# BlindController.net
KiCad netlist of a schematic drawn in Altium Designer
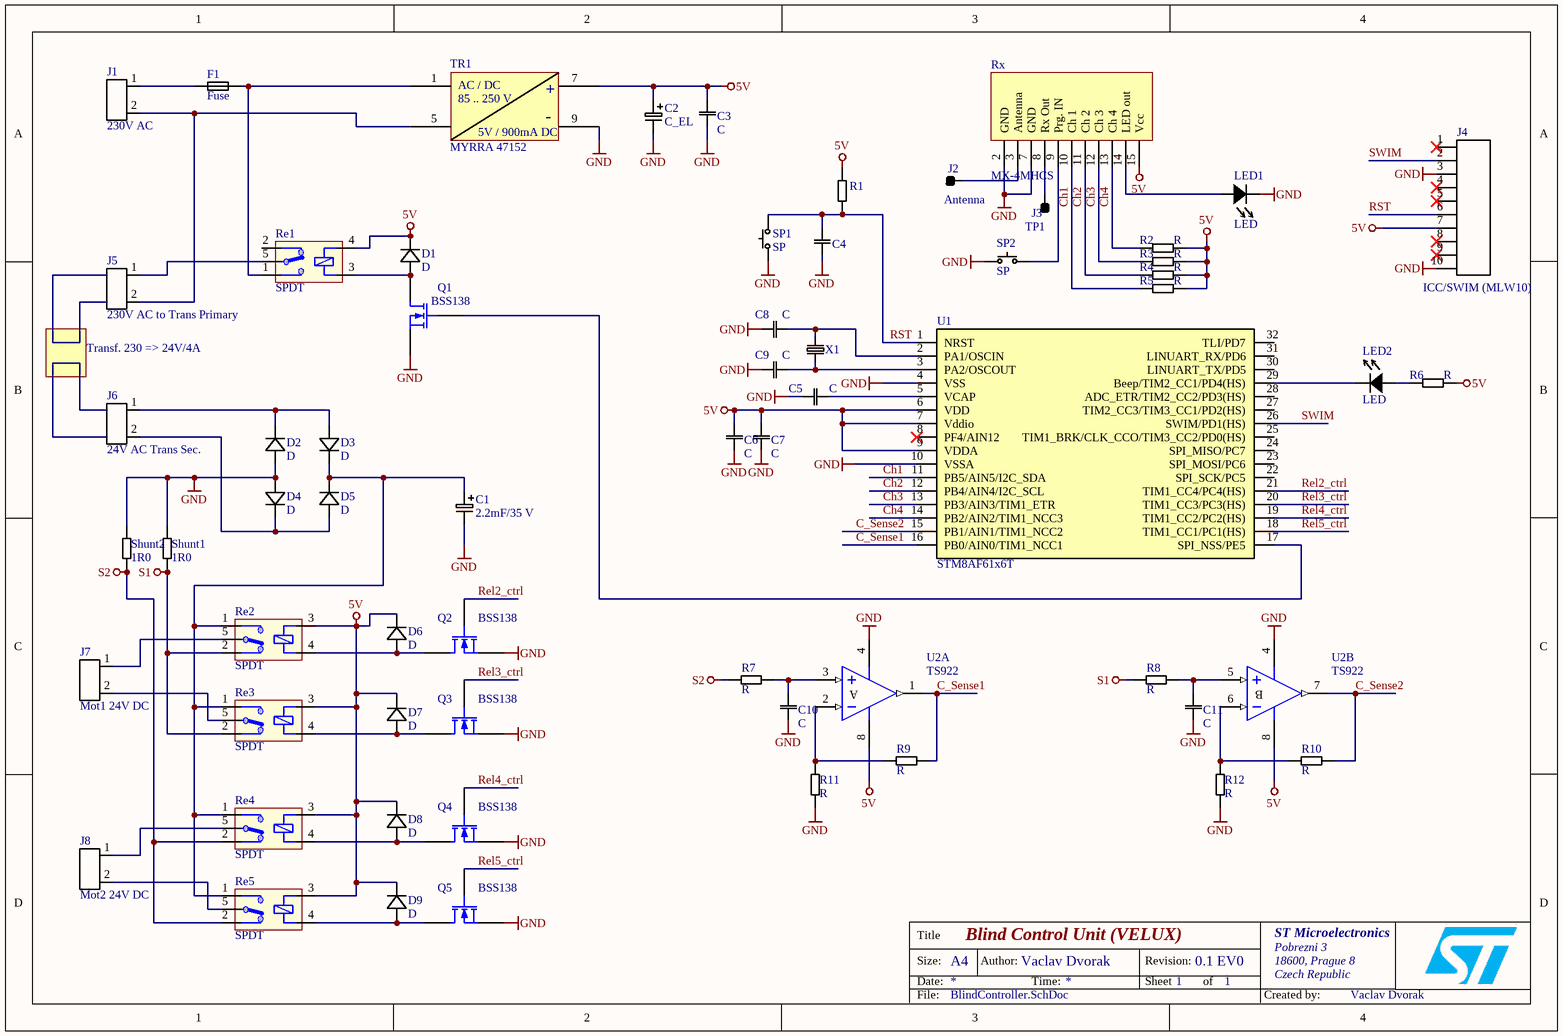
[diagram p0: BlindController.SchDoc]

(export (version "E")
  (design (tool "Eeschema 10.0.6"))
  (components
    (comp (ref "C1")
      (value "2.2mF/35 V")
      (footprint "EL_10X13")
      (libsource (lib "ABU_standard") (part "C_EL_1"))
    )
    (comp (ref "C2") (value "C_EL") (footprint "EL_5x11") (libsource (lib "ABU_standard") (part "C_EL")))
    (comp (ref "C3") (value "C") (footprint "ABU_standard:C0805") (libsource (lib "ABU_standard") (part "C")))
    (comp (ref "C4") (value "~") (footprint "ABU_standard:C0805") (libsource (lib "*") (part "C")))
    (comp (ref "C5") (value "C") (footprint "C0805") (libsource (lib "ABU_standard") (part "C")))
    (comp (ref "C6") (value "C") (footprint "ABU_standard:C0805") (libsource (lib "ABU_standard") (part "C")))
    (comp (ref "C7") (value "C") (footprint "ABU_standard:C0805") (libsource (lib "ABU_standard") (part "C")))
    (comp (ref "C8") (value "C") (footprint "ABU_standard:C0805") (libsource (lib "ABU_STANDARD") (part "C")))
    (comp (ref "C9") (value "C") (footprint "ABU_standard:C0805") (libsource (lib "ABU_STANDARD") (part "C")))
    (comp (ref "C10")
      (value "C")
      (footprint "ABU_standard:C0805")
      (libsource (lib "ABU_standard") (part "C"))
    )
    (comp (ref "C11")
      (value "C")
      (footprint "ABU_standard:C0805")
      (libsource (lib "ABU_standard") (part "C"))
    )
    (comp (ref "D1") (value "D") (footprint "SMA") (libsource (lib "ABU_standard") (part "D")))
    (comp (ref "D2") (value "D") (footprint "DO41") (libsource (lib "ABU_standard") (part "D")))
    (comp (ref "D3") (value "D") (footprint "DO41") (libsource (lib "ABU_standard") (part "D")))
    (comp (ref "D4") (value "D") (footprint "DO41") (libsource (lib "ABU_standard") (part "D")))
    (comp (ref "D5") (value "D") (footprint "DO41") (libsource (lib "ABU_standard") (part "D")))
    (comp (ref "D6") (value "D") (footprint "SMA") (libsource (lib "ABU_standard") (part "D")))
    (comp (ref "D7") (value "D") (footprint "SMA") (libsource (lib "ABU_standard") (part "D")))
    (comp (ref "D8") (value "D") (footprint "SMA") (libsource (lib "ABU_standard") (part "D")))
    (comp (ref "D9") (value "D") (footprint "SMA") (libsource (lib "ABU_standard") (part "D")))
    (comp (ref "F1") (value "Fuse") (footprint "AXIAL-0.5L") (libsource (lib "Private") (part "Fuse")))
    (comp (ref "J1") (value "230V AC") (footprint "ARK_2") (libsource (lib "ABU_standard") (part "CON_2")))
    (comp (ref "J2") (value "Antenna") (footprint "PIN") (libsource (lib "ABU_standard") (part "PIN")))
    (comp (ref "J3") (value "TP1") (footprint "PIN") (libsource (lib "") (part "PIN_1")))
    (comp (ref "J4") (value "ICC/SWIM (MLW10)") (footprint "MLW10") (libsource (lib "*") (part "CON_10")))
    (comp (ref "J5")
      (value "230V AC to Trans Primary")
      (footprint "ARK_2")
      (libsource (lib "ABU_standard") (part "CON_2"))
    )
    (comp (ref "J6")
      (value "24V AC Trans Sec.")
      (footprint "ARK_2")
      (libsource (lib "ABU_standard") (part "CON_2"))
    )
    (comp (ref "J7")
      (value "Mot1 24V DC")
      (footprint "ARK_2")
      (libsource (lib "ABU_standard") (part "CON_2"))
    )
    (comp (ref "J8")
      (value "Mot2 24V DC")
      (footprint "ARK_2")
      (libsource (lib "ABU_standard") (part "CON_2"))
    )
    (comp (ref "LED1") (value "LED") (footprint "LED_SMD") (libsource (lib "ABU_standard") (part "LED")))
    (comp (ref "LED2") (value "LED") (footprint "LED_SMD") (libsource (lib "ABU_standard") (part "LED")))
    (comp (ref "Q1")
      (value "BSS138")
      (footprint "SOT23")
      (description "N-Channel Enhancement Mode Vertical DMOS FET")
      (fields (field (name "PUBLISHER") "Altium Limited"))
      (libsource (lib "ABU_standard") (part "BSS138"))
    )
    (comp (ref "Q2")
      (value "BSS138")
      (footprint "SOT23")
      (description "N-Channel Enhancement Mode Vertical DMOS FET")
      (fields (field (name "PUBLISHER") "Altium Limited"))
      (libsource (lib "ABU_standard") (part "BSS138"))
    )
    (comp (ref "Q3")
      (value "BSS138")
      (footprint "SOT23")
      (description "N-Channel Enhancement Mode Vertical DMOS FET")
      (fields (field (name "PUBLISHER") "Altium Limited"))
      (libsource (lib "ABU_standard") (part "BSS138"))
    )
    (comp (ref "Q4")
      (value "BSS138")
      (footprint "SOT23")
      (description "N-Channel Enhancement Mode Vertical DMOS FET")
      (fields (field (name "PUBLISHER") "Altium Limited"))
      (libsource (lib "ABU_standard") (part "BSS138"))
    )
    (comp (ref "Q5")
      (value "BSS138")
      (footprint "SOT23")
      (description "N-Channel Enhancement Mode Vertical DMOS FET")
      (fields (field (name "PUBLISHER") "Altium Limited"))
      (libsource (lib "ABU_standard") (part "BSS138"))
    )
    (comp (ref "R1") (value "~") (footprint "R0805") (libsource (lib "*") (part "R")))
    (comp (ref "R2") (value "R") (footprint "R0805") (libsource (lib "ABU_standard") (part "R")))
    (comp (ref "R3") (value "R") (footprint "R0805") (libsource (lib "ABU_standard") (part "R")))
    (comp (ref "R4") (value "R") (footprint "R0805") (libsource (lib "ABU_standard") (part "R")))
    (comp (ref "R5") (value "R") (footprint "R0805") (libsource (lib "ABU_standard") (part "R")))
    (comp (ref "R6") (value "R") (footprint "R0805") (libsource (lib "ABU_standard") (part "R")))
    (comp (ref "R7") (value "R") (footprint "R0805") (libsource (lib "") (part "R_2")))
    (comp (ref "R8") (value "R") (footprint "R0805") (libsource (lib "") (part "R_2")))
    (comp (ref "R9") (value "R") (footprint "R0805") (libsource (lib "ABU_standard") (part "R")))
    (comp (ref "R10") (value "R") (footprint "R0805") (libsource (lib "ABU_standard") (part "R")))
    (comp (ref "R11") (value "R") (footprint "R0805") (libsource (lib "") (part "R_1")))
    (comp (ref "R12") (value "R") (footprint "R0805") (libsource (lib "") (part "R_1")))
    (comp (ref "Re1")
      (value "SPDT")
      (footprint "Rele_JS-K")
      (description "rele SPDT")
      (libsource (lib "") (part "Rele_SPDT_1"))
    )
    (comp (ref "Re2")
      (value "SPDT")
      (footprint "Rele_JS-K")
      (description "rele SPDT")
      (libsource (lib "Private") (part "Rele_SPDT"))
    )
    (comp (ref "Re3")
      (value "SPDT")
      (footprint "Rele_JS-K")
      (description "rele SPDT")
      (libsource (lib "Private") (part "Rele_SPDT"))
    )
    (comp (ref "Re4")
      (value "SPDT")
      (footprint "Rele_JS-K")
      (description "rele SPDT")
      (libsource (lib "Private") (part "Rele_SPDT"))
    )
    (comp (ref "Re5")
      (value "SPDT")
      (footprint "Rele_JS-K")
      (description "rele SPDT")
      (libsource (lib "Private") (part "Rele_SPDT"))
    )
    (comp (ref "Rx") (value "MX-4MHCS") (footprint "RX-4MHCS") (libsource (lib "Private") (part "RX-4MHCS")))
    (comp (ref "Shunt1") (value "1R0") (footprint "R Shunt S-2") (libsource (lib "") (part "R_1")))
    (comp (ref "Shunt2") (value "1R0") (footprint "R Shunt S-2") (libsource (lib "") (part "R_1")))
    (comp (ref "SP1") (value "SP") (footprint "DIP_PUSH_BUTTON") (libsource (lib "*") (part "SP")))
    (comp (ref "SP2") (value "SP") (footprint "DIP_PUSH_BUTTON") (libsource (lib "ABU_standard") (part "SP")))
    (comp (ref "TR1")
      (value "MYRRA 47152")
      (footprint "Private:Myrra47000")
      (description "AC/DC  IN:85..260 V AC(DC), OUT: 5V/900mA DC")
      (libsource (lib "Private") (part "MYRRA_AC_DC"))
    )
    (comp (ref "U1")
      (value "STM8AF61x6T")
      (footprint "QFP32")
      (libsource (lib "ABU_standard") (part "STM8AF61x6T"))
    )
    (comp (ref "U2")
      (value "TS922")
      (footprint "SO8_L")
      (description "Rail-to-Rail CMOS Dual Operational Amplifier")
      (fields (field (name "PUBLISHER") "Altium Limited"))
      (libsource (lib "ST Operational Amplifier") (part "TS912ID"))
    )
    (comp (ref "X1") (value "~") (footprint "HC-49U") (libsource (lib "ABU_STANDARD") (part "XTALL")))
  )
  (nets
    (net (code "1") (name "/C_Sense1") (class "Default")
      (node (ref "R9") (pin "1") (pinfunction "1_1") (pintype "passive"))
      (node (ref "U1") (pin "16") (pinfunction "PB0/AIN0/TIM1_NCC1_16") (pintype "passive"))
      (node (ref "U2") (pin "1") (pinfunction "OUT_1") (pintype "output"))
    )
    (net (code "2") (name "/C_Sense2") (class "Default")
      (node (ref "R10") (pin "1") (pinfunction "1_1") (pintype "passive"))
      (node (ref "U1") (pin "15") (pinfunction "PB1/AIN1/TIM1_NCC2_15") (pintype "passive"))
      (node (ref "U2") (pin "7") (pinfunction "OUT_7") (pintype "output"))
    )
    (net (code "3") (name "/Ch1") (class "Default")
      (node (ref "R5") (pin "2") (pinfunction "2_2") (pintype "passive"))
      (node (ref "Rx") (pin "10") (pinfunction "Ch_1_10") (pintype "passive"))
      (node (ref "U1") (pin "11") (pinfunction "PB5/AIN5/I2C_SDA_11") (pintype "passive"))
    )
    (net (code "4") (name "/Ch2") (class "Default")
      (node (ref "R4") (pin "2") (pinfunction "2_2") (pintype "passive"))
      (node (ref "Rx") (pin "11") (pinfunction "Ch_2_11") (pintype "passive"))
      (node (ref "U1") (pin "12") (pinfunction "PB4/AIN4/I2C_SCL_12") (pintype "passive"))
    )
    (net (code "5") (name "/Ch3") (class "Default")
      (node (ref "R3") (pin "2") (pinfunction "2_2") (pintype "passive"))
      (node (ref "Rx") (pin "12") (pinfunction "Ch_3_12") (pintype "passive"))
      (node (ref "U1") (pin "13") (pinfunction "PB3/AIN3/TIM1_ETR_13") (pintype "passive"))
    )
    (net (code "6") (name "/Ch4") (class "Default")
      (node (ref "R2") (pin "2") (pinfunction "2_2") (pintype "passive"))
      (node (ref "Rx") (pin "13") (pinfunction "Ch_4_13") (pintype "passive"))
      (node (ref "U1") (pin "14") (pinfunction "PB2/AIN2/TIM1_NCC3_14") (pintype "passive"))
    )
    (net (code "7") (name "/RST") (class "Default")
      (node (ref "C4") (pin "2") (pinfunction "2_2") (pintype "passive"))
      (node (ref "J4") (pin "6") (pinfunction "6_6") (pintype "passive"))
      (node (ref "R1") (pin "2") (pinfunction "2_2") (pintype "passive"))
      (node (ref "SP1") (pin "2") (pinfunction "2_2") (pintype "passive"))
      (node (ref "U1") (pin "1") (pinfunction "NRST_1") (pintype "passive"))
    )
    (net (code "8") (name "/Rel2_ctrl") (class "Default")
      (node (ref "Q2") (pin "1") (pinfunction "G_1") (pintype "passive"))
      (node (ref "U1") (pin "21") (pinfunction "TIM1_CC4/PC4(HS)_21") (pintype "passive"))
    )
    (net (code "9") (name "/Rel3_ctrl") (class "Default")
      (node (ref "Q3") (pin "1") (pinfunction "G_1") (pintype "passive"))
      (node (ref "U1") (pin "20") (pinfunction "TIM1_CC3/PC3(HS)_20") (pintype "passive"))
    )
    (net (code "10") (name "/Rel4_ctrl") (class "Default")
      (node (ref "Q4") (pin "1") (pinfunction "G_1") (pintype "passive"))
      (node (ref "U1") (pin "19") (pinfunction "TIM1_CC2/PC2(HS)_19") (pintype "passive"))
    )
    (net (code "11") (name "/Rel5_ctrl") (class "Default")
      (node (ref "Q5") (pin "1") (pinfunction "G_1") (pintype "passive"))
      (node (ref "U1") (pin "18") (pinfunction "TIM1_CC1/PC1(HS)_18") (pintype "passive"))
    )
    (net (code "12") (name "/SWIM") (class "Default")
      (node (ref "J4") (pin "2") (pinfunction "2_2") (pintype "passive"))
      (node (ref "U1") (pin "26") (pinfunction "SWIM/PD1(HS)_26") (pintype "passive"))
    )
    (net (code "13") (name "5V") (class "Default")
      (node (ref "C2") (pin "1") (pinfunction "1_1") (pintype "passive"))
      (node (ref "C3") (pin "2") (pinfunction "2_2") (pintype "passive"))
      (node (ref "C6") (pin "2") (pinfunction "2_2") (pintype "passive"))
      (node (ref "C7") (pin "2") (pinfunction "2_2") (pintype "passive"))
      (node (ref "D1") (pin "2") (pinfunction "K_2") (pintype "passive"))
      (node (ref "D6") (pin "2") (pinfunction "K_2") (pintype "passive"))
      (node (ref "D7") (pin "2") (pinfunction "K_2") (pintype "passive"))
      (node (ref "D8") (pin "2") (pinfunction "K_2") (pintype "passive"))
      (node (ref "D9") (pin "2") (pinfunction "K_2") (pintype "passive"))
      (node (ref "J4") (pin "7") (pinfunction "7_7") (pintype "passive"))
      (node (ref "R1") (pin "1") (pinfunction "1_1") (pintype "passive"))
      (node (ref "R2") (pin "1") (pinfunction "1_1") (pintype "passive"))
      (node (ref "R3") (pin "1") (pinfunction "1_1") (pintype "passive"))
      (node (ref "R4") (pin "1") (pinfunction "1_1") (pintype "passive"))
      (node (ref "R5") (pin "1") (pinfunction "1_1") (pintype "passive"))
      (node (ref "R6") (pin "1") (pinfunction "1_1") (pintype "passive"))
      (node (ref "Re1") (pin "4") (pinfunction "4_4") (pintype "passive"))
      (node (ref "Re2") (pin "3") (pinfunction "3_3") (pintype "passive"))
      (node (ref "Re3") (pin "3") (pinfunction "3_3") (pintype "passive"))
      (node (ref "Re4") (pin "3") (pinfunction "3_3") (pintype "passive"))
      (node (ref "Re5") (pin "3") (pinfunction "3_3") (pintype "passive"))
      (node (ref "Rx") (pin "15") (pinfunction "Vcc_15") (pintype "passive"))
      (node (ref "TR1") (pin "7") (pinfunction "7_7") (pintype "passive"))
      (node (ref "U1") (pin "6") (pinfunction "VDD_6") (pintype "passive"))
      (node (ref "U1") (pin "7") (pinfunction "Vddio_7") (pintype "passive"))
      (node (ref "U1") (pin "9") (pinfunction "VDDA_9") (pintype "passive"))
      (node (ref "U2") (pin "8") (pinfunction "V+_8") (pintype "power_in"))
    )
    (net (code "14") (name "GND") (class "Default")
      (node (ref "C1") (pin "2") (pinfunction "2_2") (pintype "passive"))
      (node (ref "C10") (pin "1") (pinfunction "1_1") (pintype "passive"))
      (node (ref "C11") (pin "1") (pinfunction "1_1") (pintype "passive"))
      (node (ref "C2") (pin "2") (pinfunction "2_2") (pintype "passive"))
      (node (ref "C3") (pin "1") (pinfunction "1_1") (pintype "passive"))
      (node (ref "C4") (pin "1") (pinfunction "1_1") (pintype "passive"))
      (node (ref "C5") (pin "1") (pinfunction "1_1") (pintype "passive"))
      (node (ref "C6") (pin "1") (pinfunction "1_1") (pintype "passive"))
      (node (ref "C7") (pin "1") (pinfunction "1_1") (pintype "passive"))
      (node (ref "C8") (pin "1") (pinfunction "1_1") (pintype "passive"))
      (node (ref "C9") (pin "1") (pinfunction "1_1") (pintype "passive"))
      (node (ref "D2") (pin "1") (pinfunction "A_1") (pintype "passive"))
      (node (ref "D4") (pin "1") (pinfunction "A_1") (pintype "passive"))
      (node (ref "J4") (pin "10") (pinfunction "10_10") (pintype "passive"))
      (node (ref "J4") (pin "3") (pinfunction "3_3") (pintype "passive"))
      (node (ref "LED1") (pin "2") (pinfunction "K_2") (pintype "passive"))
      (node (ref "Q1") (pin "2") (pinfunction "S_2") (pintype "passive"))
      (node (ref "Q2") (pin "2") (pinfunction "S_2") (pintype "passive"))
      (node (ref "Q3") (pin "2") (pinfunction "S_2") (pintype "passive"))
      (node (ref "Q4") (pin "2") (pinfunction "S_2") (pintype "passive"))
      (node (ref "Q5") (pin "2") (pinfunction "S_2") (pintype "passive"))
      (node (ref "R11") (pin "2") (pinfunction "2_2") (pintype "passive"))
      (node (ref "R12") (pin "2") (pinfunction "2_2") (pintype "passive"))
      (node (ref "Rx") (pin "2") (pinfunction "GND_2") (pintype "passive"))
      (node (ref "Rx") (pin "7") (pinfunction "GND_7") (pintype "passive"))
      (node (ref "SP1") (pin "1") (pinfunction "1_1") (pintype "passive"))
      (node (ref "SP2") (pin "1") (pinfunction "1_1") (pintype "passive"))
      (node (ref "Shunt1") (pin "1") (pinfunction "1_1") (pintype "passive"))
      (node (ref "Shunt2") (pin "1") (pinfunction "1_1") (pintype "passive"))
      (node (ref "TR1") (pin "9") (pinfunction "9_9") (pintype "passive"))
      (node (ref "U1") (pin "10") (pinfunction "VSSA_10") (pintype "passive"))
      (node (ref "U1") (pin "4") (pinfunction "VSS_4") (pintype "passive"))
      (node (ref "U2") (pin "4") (pinfunction "V-_4") (pintype "power_in"))
    )
    (net (code "15") (name "Net-(D1-A)") (class "Default")
      (node (ref "D1") (pin "1") (pinfunction "A_1") (pintype "passive"))
      (node (ref "Q1") (pin "3") (pinfunction "D_3") (pintype "passive"))
      (node (ref "Re1") (pin "3") (pinfunction "3_3") (pintype "passive"))
    )
    (net (code "16") (name "Net-(D2-K)") (class "Default")
      (node (ref "D2") (pin "2") (pinfunction "K_2") (pintype "passive"))
      (node (ref "D3") (pin "1") (pinfunction "A_1") (pintype "passive"))
      (node (ref "J6") (pin "1") (pinfunction "1_1") (pintype "passive"))
    )
    (net (code "17") (name "Net-(D3-K)") (class "Default")
      (node (ref "C1") (pin "1") (pinfunction "1_1") (pintype "passive"))
      (node (ref "D3") (pin "2") (pinfunction "K_2") (pintype "passive"))
      (node (ref "D5") (pin "2") (pinfunction "K_2") (pintype "passive"))
      (node (ref "Re2") (pin "1") (pinfunction "1_1") (pintype "passive"))
      (node (ref "Re3") (pin "1") (pinfunction "1_1") (pintype "passive"))
      (node (ref "Re4") (pin "1") (pinfunction "1_1") (pintype "passive"))
      (node (ref "Re5") (pin "1") (pinfunction "1_1") (pintype "passive"))
    )
    (net (code "18") (name "Net-(D4-K)") (class "Default")
      (node (ref "D4") (pin "2") (pinfunction "K_2") (pintype "passive"))
      (node (ref "D5") (pin "1") (pinfunction "A_1") (pintype "passive"))
      (node (ref "J6") (pin "2") (pinfunction "2_2") (pintype "passive"))
    )
    (net (code "19") (name "Net-(D6-A)") (class "Default")
      (node (ref "D6") (pin "1") (pinfunction "A_1") (pintype "passive"))
      (node (ref "Q2") (pin "3") (pinfunction "D_3") (pintype "passive"))
      (node (ref "Re2") (pin "4") (pinfunction "4_4") (pintype "passive"))
    )
    (net (code "20") (name "Net-(D7-A)") (class "Default")
      (node (ref "D7") (pin "1") (pinfunction "A_1") (pintype "passive"))
      (node (ref "Q3") (pin "3") (pinfunction "D_3") (pintype "passive"))
      (node (ref "Re3") (pin "4") (pinfunction "4_4") (pintype "passive"))
    )
    (net (code "21") (name "Net-(D8-A)") (class "Default")
      (node (ref "D8") (pin "1") (pinfunction "A_1") (pintype "passive"))
      (node (ref "Q4") (pin "3") (pinfunction "D_3") (pintype "passive"))
      (node (ref "Re4") (pin "4") (pinfunction "4_4") (pintype "passive"))
    )
    (net (code "22") (name "Net-(D9-A)") (class "Default")
      (node (ref "D9") (pin "1") (pinfunction "A_1") (pintype "passive"))
      (node (ref "Q5") (pin "3") (pinfunction "D_3") (pintype "passive"))
      (node (ref "Re5") (pin "4") (pinfunction "4_4") (pintype "passive"))
    )
    (net (code "23") (name "Net-(F1-Pad1)") (class "Default")
      (node (ref "F1") (pin "1") (pinfunction "1_1") (pintype "passive"))
      (node (ref "Re1") (pin "1") (pinfunction "1_1") (pintype "passive"))
      (node (ref "TR1") (pin "1") (pinfunction "1_1") (pintype "passive"))
    )
    (net (code "24") (name "Net-(F1-Pad2)") (class "Default")
      (node (ref "F1") (pin "2") (pinfunction "2_2") (pintype "passive"))
      (node (ref "J1") (pin "1") (pinfunction "1_1") (pintype "passive"))
    )
    (net (code "25") (name "Net-(J1-Pad2)") (class "Default")
      (node (ref "J1") (pin "2") (pinfunction "2_2") (pintype "passive"))
      (node (ref "J5") (pin "2") (pinfunction "2_2") (pintype "passive"))
      (node (ref "TR1") (pin "5") (pinfunction "5_5") (pintype "passive"))
    )
    (net (code "26") (name "Net-(J5-Pad1)") (class "Default")
      (node (ref "J5") (pin "1") (pinfunction "1_1") (pintype "passive"))
      (node (ref "Re1") (pin "5") (pinfunction "5_5") (pintype "passive"))
    )
    (net (code "27") (name "Net-(J7-Pad1)") (class "Default")
      (node (ref "J7") (pin "1") (pinfunction "1_1") (pintype "passive"))
      (node (ref "Re2") (pin "5") (pinfunction "5_5") (pintype "passive"))
    )
    (net (code "28") (name "Net-(J7-Pad2)") (class "Default")
      (node (ref "J7") (pin "2") (pinfunction "2_2") (pintype "passive"))
      (node (ref "Re3") (pin "5") (pinfunction "5_5") (pintype "passive"))
    )
    (net (code "29") (name "Net-(J8-Pad1)") (class "Default")
      (node (ref "J8") (pin "1") (pinfunction "1_1") (pintype "passive"))
      (node (ref "Re4") (pin "5") (pinfunction "5_5") (pintype "passive"))
    )
    (net (code "30") (name "Net-(J8-Pad2)") (class "Default")
      (node (ref "J8") (pin "2") (pinfunction "2_2") (pintype "passive"))
      (node (ref "Re5") (pin "5") (pinfunction "5_5") (pintype "passive"))
    )
    (net (code "31") (name "Net-(LED1-A)") (class "Default")
      (node (ref "LED1") (pin "1") (pinfunction "A_1") (pintype "passive"))
      (node (ref "Rx") (pin "14") (pinfunction "LED_out_14") (pintype "passive"))
    )
    (net (code "32") (name "Net-(LED2-A)") (class "Default")
      (node (ref "LED2") (pin "1") (pinfunction "A_1") (pintype "passive"))
      (node (ref "R6") (pin "2") (pinfunction "2_2") (pintype "passive"))
    )
    (net (code "33") (name "Net-(LED2-K)") (class "Default")
      (node (ref "LED2") (pin "2") (pinfunction "K_2") (pintype "passive"))
      (node (ref "U1") (pin "29") (pinfunction "Beep/TIM2_CC1/PD4(HS)_29") (pintype "passive"))
    )
    (net (code "34") (name "Net-(Q1-G)") (class "Default")
      (node (ref "Q1") (pin "1") (pinfunction "G_1") (pintype "passive"))
      (node (ref "U1") (pin "17") (pinfunction "SPI_NSS/PE5_17") (pintype "passive"))
    )
    (net (code "35") (name "Net-(Rx-Antenna)") (class "Default")
      (node (ref "J2") (pin "1") (pinfunction "1_1") (pintype "passive"))
      (node (ref "Rx") (pin "3") (pinfunction "Antenna_3") (pintype "passive"))
    )
    (net (code "36") (name "Net-(Rx-Prg._IN)") (class "Default")
      (node (ref "Rx") (pin "9") (pinfunction "Prg._IN_9") (pintype "passive"))
      (node (ref "SP2") (pin "2") (pinfunction "2_2") (pintype "passive"))
    )
    (net (code "37") (name "Net-(Rx-Rx_Out)") (class "Default")
      (node (ref "J3") (pin "1") (pinfunction "1_1") (pintype "passive"))
      (node (ref "Rx") (pin "8") (pinfunction "Rx_Out_8") (pintype "passive"))
    )
    (net (code "38") (name "Net-(U1-PA1{slash}OSCIN)") (class "Default")
      (node (ref "C8") (pin "2") (pinfunction "2_2") (pintype "passive"))
      (node (ref "U1") (pin "2") (pinfunction "PA1/OSCIN_2") (pintype "passive"))
      (node (ref "X1") (pin "1") (pinfunction "1_1") (pintype "passive"))
    )
    (net (code "39") (name "Net-(U1-PA2{slash}OSCOUT)") (class "Default")
      (node (ref "C9") (pin "2") (pinfunction "2_2") (pintype "passive"))
      (node (ref "U1") (pin "3") (pinfunction "PA2/OSCOUT_3") (pintype "passive"))
      (node (ref "X1") (pin "2") (pinfunction "2_2") (pintype "passive"))
    )
    (net (code "40") (name "Net-(U1-VCAP)") (class "Default")
      (node (ref "C5") (pin "2") (pinfunction "2_2") (pintype "passive"))
      (node (ref "U1") (pin "5") (pinfunction "VCAP_5") (pintype "passive"))
    )
    (net (code "41") (name "Net-(U2A-IN+)") (class "Default")
      (node (ref "C10") (pin "2") (pinfunction "2_2") (pintype "passive"))
      (node (ref "R7") (pin "2") (pinfunction "2_2") (pintype "passive"))
      (node (ref "U2") (pin "3") (pinfunction "IN+_3") (pintype "input"))
    )
    (net (code "42") (name "Net-(U2A-IN-)") (class "Default")
      (node (ref "R11") (pin "1") (pinfunction "1_1") (pintype "passive"))
      (node (ref "R9") (pin "2") (pinfunction "2_2") (pintype "passive"))
      (node (ref "U2") (pin "2") (pinfunction "IN-_2") (pintype "input"))
    )
    (net (code "43") (name "Net-(U2B-IN+)") (class "Default")
      (node (ref "C11") (pin "2") (pinfunction "2_2") (pintype "passive"))
      (node (ref "R8") (pin "2") (pinfunction "2_2") (pintype "passive"))
      (node (ref "U2") (pin "5") (pinfunction "IN+_5") (pintype "input"))
    )
    (net (code "44") (name "Net-(U2B-IN-)") (class "Default")
      (node (ref "R10") (pin "2") (pinfunction "2_2") (pintype "passive"))
      (node (ref "R12") (pin "1") (pinfunction "1_1") (pintype "passive"))
      (node (ref "U2") (pin "6") (pinfunction "IN-_6") (pintype "input"))
    )
    (net (code "45") (name "S1") (class "Default")
      (node (ref "R8") (pin "1") (pinfunction "1_1") (pintype "passive"))
      (node (ref "Re2") (pin "2") (pinfunction "2_2") (pintype "passive"))
      (node (ref "Re3") (pin "2") (pinfunction "2_2") (pintype "passive"))
      (node (ref "Shunt1") (pin "2") (pinfunction "2_2") (pintype "passive"))
    )
    (net (code "46") (name "S2") (class "Default")
      (node (ref "R7") (pin "1") (pinfunction "1_1") (pintype "passive"))
      (node (ref "Re4") (pin "2") (pinfunction "2_2") (pintype "passive"))
      (node (ref "Re5") (pin "2") (pinfunction "2_2") (pintype "passive"))
      (node (ref "Shunt2") (pin "2") (pinfunction "2_2") (pintype "passive"))
    )
    (net (code "47") (name "unconnected-(J4-Pad1)") (class "Default")
      (node (ref "J4") (pin "1") (pinfunction "1_1") (pintype "passive+no_connect"))
    )
    (net (code "48") (name "unconnected-(J4-Pad4)") (class "Default")
      (node (ref "J4") (pin "4") (pinfunction "4_4") (pintype "passive+no_connect"))
    )
    (net (code "49") (name "unconnected-(J4-Pad5)") (class "Default")
      (node (ref "J4") (pin "5") (pinfunction "5_5") (pintype "passive+no_connect"))
    )
    (net (code "50") (name "unconnected-(J4-Pad8)") (class "Default")
      (node (ref "J4") (pin "8") (pinfunction "8_8") (pintype "passive+no_connect"))
    )
    (net (code "51") (name "unconnected-(J4-Pad9)") (class "Default")
      (node (ref "J4") (pin "9") (pinfunction "9_9") (pintype "passive+no_connect"))
    )
    (net (code "52") (name "unconnected-(Re1-Pad2)") (class "Default")
      (node (ref "Re1") (pin "2") (pinfunction "2_2") (pintype "passive"))
    )
    (net (code "53") (name "unconnected-(U1-ADC_ETR{slash}TIM2_CC2{slash}PD3(HS)-Pad28)") (class "Default")
      (node (ref "U1") (pin "28") (pinfunction "ADC_ETR/TIM2_CC2/PD3(HS)_28") (pintype "passive"))
    )
    (net (code "54") (name "unconnected-(U1-LINUART_RX{slash}PD6-Pad31)") (class "Default")
      (node (ref "U1") (pin "31") (pinfunction "LINUART_RX/PD6_31") (pintype "passive"))
    )
    (net (code "55") (name "unconnected-(U1-LINUART_TX{slash}PD5-Pad30)") (class "Default")
      (node (ref "U1") (pin "30") (pinfunction "LINUART_TX/PD5_30") (pintype "passive"))
    )
    (net (code "56") (name "unconnected-(U1-PF4{slash}AIN12-Pad8)") (class "Default")
      (node (ref "U1") (pin "8") (pinfunction "PF4/AIN12_8") (pintype "passive+no_connect"))
    )
    (net (code "57") (name "unconnected-(U1-SPI_MISO{slash}PC7-Pad24)") (class "Default")
      (node (ref "U1") (pin "24") (pinfunction "SPI_MISO/PC7_24") (pintype "passive"))
    )
    (net (code "58") (name "unconnected-(U1-SPI_MOSI{slash}PC6-Pad23)") (class "Default")
      (node (ref "U1") (pin "23") (pinfunction "SPI_MOSI/PC6_23") (pintype "passive"))
    )
    (net (code "59") (name "unconnected-(U1-SPI_SCK{slash}PC5-Pad22)") (class "Default")
      (node (ref "U1") (pin "22") (pinfunction "SPI_SCK/PC5_22") (pintype "passive"))
    )
    (net (code "60") (name "unconnected-(U1-TIM1_BRK{slash}CLK_CCO{slash}TIM3_CC2{slash}PD0(HS)-Pad25)") (class "Default")
      (node (ref "U1") (pin "25") (pinfunction "TIM1_BRK/CLK_CCO/TIM3_CC2/PD0(HS)_25") (pintype "passive"))
    )
    (net (code "61") (name "unconnected-(U1-TIM2_CC3{slash}TIM3_CC1{slash}PD2(HS)-Pad27)") (class "Default")
      (node (ref "U1") (pin "27") (pinfunction "TIM2_CC3/TIM3_CC1/PD2(HS)_27") (pintype "passive"))
    )
    (net (code "62") (name "unconnected-(U1-TLI{slash}PD7-Pad32)") (class "Default")
      (node (ref "U1") (pin "32") (pinfunction "TLI/PD7_32") (pintype "passive"))
    )
  )
)
